# Pcm5102.net
KiCad netlist of a schematic drawn in EAGLE
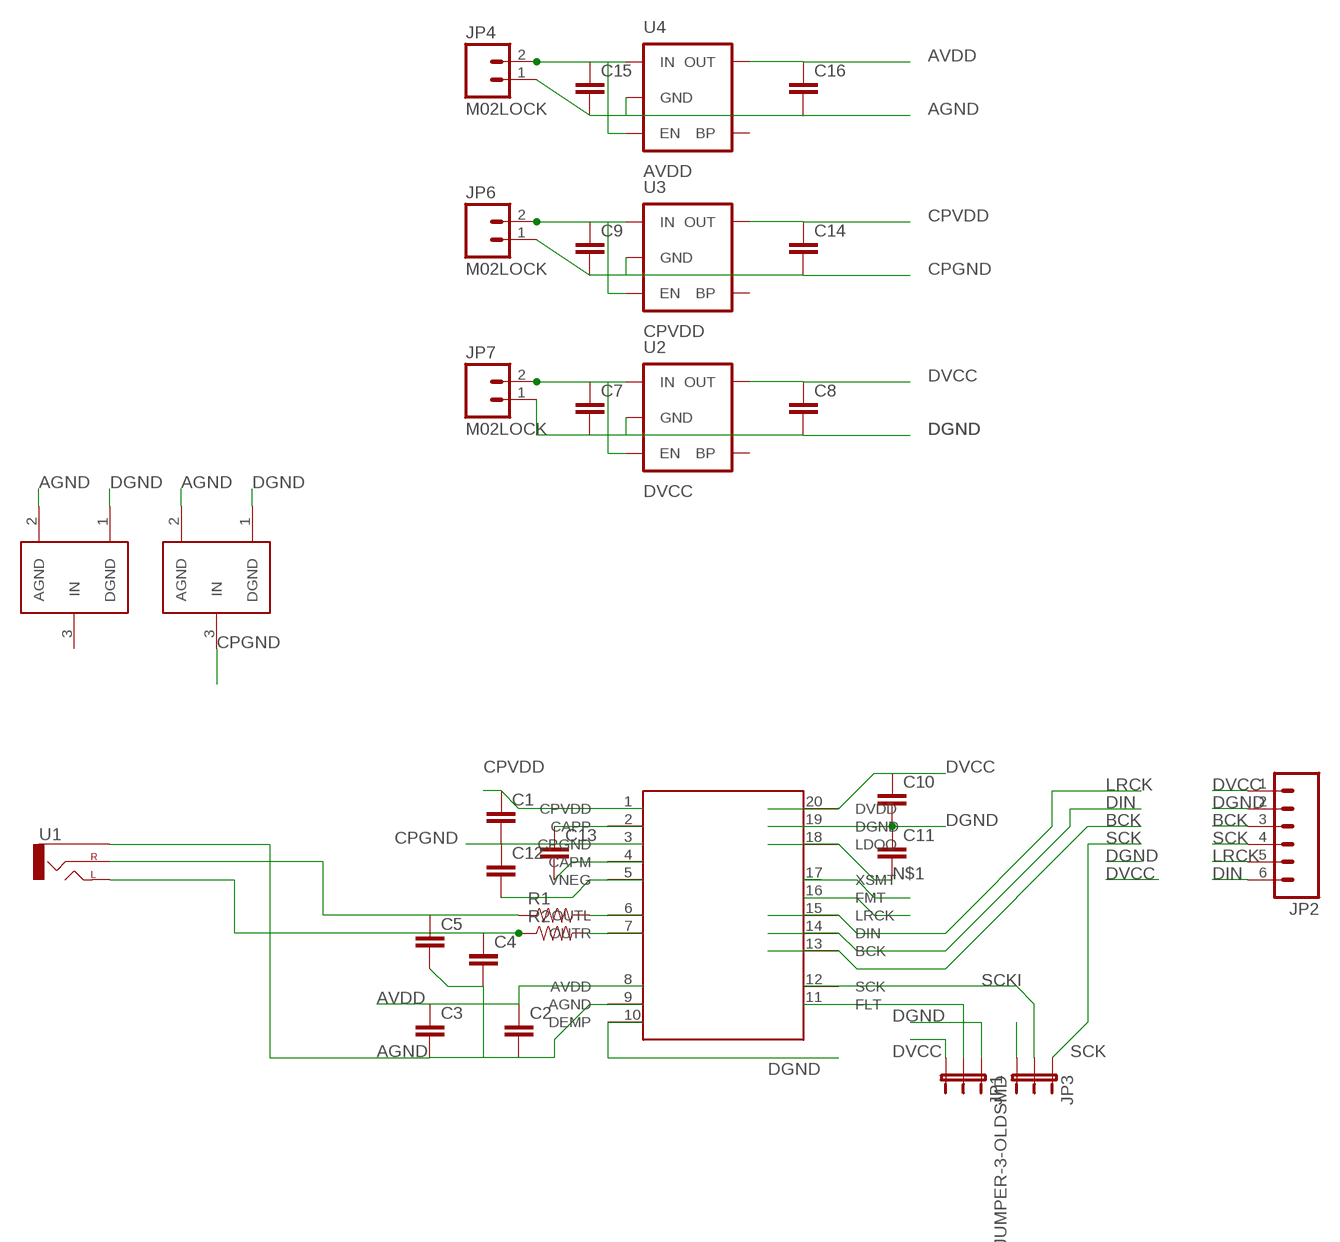
[diagram p0: schematic, sheet 1]

(export (version "E")
  (design (tool "Eeschema 10.0.6"))
  (components
    (comp (ref "C1")
      (value "CAP0805")
      (footprint "eagle-import:0805")
      (libsource (lib "eagle-import") (part "CAP0805"))
    )
    (comp (ref "C2")
      (value "CAP0805")
      (footprint "eagle-import:0805")
      (libsource (lib "eagle-import") (part "CAP0805"))
    )
    (comp (ref "C3")
      (value "CAP0805")
      (footprint "eagle-import:0805")
      (libsource (lib "eagle-import") (part "CAP0805"))
    )
    (comp (ref "C4")
      (value "CAPPTH1")
      (footprint "eagle-import:CAP-PTH-5MM")
      (libsource (lib "eagle-import") (part "CAPPTH1"))
    )
    (comp (ref "C5")
      (value "CAPPTH1")
      (footprint "eagle-import:CAP-PTH-5MM")
      (libsource (lib "eagle-import") (part "CAPPTH1"))
    )
    (comp (ref "C7")
      (value "CAP0805")
      (footprint "eagle-import:0805")
      (libsource (lib "eagle-import") (part "CAP0805"))
    )
    (comp (ref "C8")
      (value "CAP0805")
      (footprint "eagle-import:0805")
      (libsource (lib "eagle-import") (part "CAP0805"))
    )
    (comp (ref "C9")
      (value "CAP0805")
      (footprint "eagle-import:0805")
      (libsource (lib "eagle-import") (part "CAP0805"))
    )
    (comp (ref "C10")
      (value "CAP0805")
      (footprint "eagle-import:0805")
      (libsource (lib "eagle-import") (part "CAP0805"))
    )
    (comp (ref "C11")
      (value "CAP0805")
      (footprint "eagle-import:0805")
      (libsource (lib "eagle-import") (part "CAP0805"))
    )
    (comp (ref "C12")
      (value "CAP0805")
      (footprint "eagle-import:0805")
      (libsource (lib "eagle-import") (part "CAP0805"))
    )
    (comp (ref "C13")
      (value "CAP0805")
      (footprint "eagle-import:0805")
      (libsource (lib "eagle-import") (part "CAP0805"))
    )
    (comp (ref "C14")
      (value "CAP0805")
      (footprint "eagle-import:0805")
      (libsource (lib "eagle-import") (part "CAP0805"))
    )
    (comp (ref "C15")
      (value "CAP0805")
      (footprint "eagle-import:0805")
      (libsource (lib "eagle-import") (part "CAP0805"))
    )
    (comp (ref "C16")
      (value "CAP0805")
      (footprint "eagle-import:0805")
      (libsource (lib "eagle-import") (part "CAP0805"))
    )
    (comp (ref "JP1")
      (value "JUMPER-3-OLDPTH")
      (footprint "eagle-import:1X03")
      (libsource (lib "eagle-import") (part "JUMPER-3-OLDPTH"))
    )
    (comp (ref "JP2")
      (value "M06LOCK")
      (footprint "eagle-import:1X06_LOCK")
      (libsource (lib "eagle-import") (part "M06LOCK"))
    )
    (comp (ref "JP3")
      (value "JUMPER-3-OLDSMD")
      (footprint "eagle-import:SJ_3")
      (libsource (lib "eagle-import") (part "JUMPER-3-OLDSMD"))
    )
    (comp (ref "JP4")
      (value "M02LOCK")
      (footprint "eagle-import:1X02_LOCK")
      (libsource (lib "eagle-import") (part "M02LOCK"))
    )
    (comp (ref "JP6")
      (value "M02LOCK")
      (footprint "eagle-import:1X02_LOCK")
      (libsource (lib "eagle-import") (part "M02LOCK"))
    )
    (comp (ref "JP7")
      (value "M02LOCK")
      (footprint "eagle-import:1X02_LOCK")
      (libsource (lib "eagle-import") (part "M02LOCK"))
    )
    (comp (ref "R1")
      (value "RESISTORPTH-1/4W")
      (footprint "eagle-import:AXIAL-0.4")
      (libsource (lib "eagle-import") (part "RESISTORPTH-1/4W"))
    )
    (comp (ref "R2")
      (value "RESISTORPTH-1/4W")
      (footprint "eagle-import:AXIAL-0.4")
      (libsource (lib "eagle-import") (part "RESISTORPTH-1/4W"))
    )
    (comp (ref "U$1")
      (value "PCM5102")
      (footprint "eagle-import:TSSOP20")
      (libsource (lib "eagle-import") (part "PCM5102"))
    )
    (comp (ref "U$2")
      (value "GND_CONNECT")
      (footprint "eagle-import:GND_CONNECT")
      (libsource (lib "eagle-import") (part "GND_CONNECT"))
    )
    (comp (ref "U$3")
      (value "GND_CONNECT")
      (footprint "eagle-import:GND_CONNECT")
      (libsource (lib "eagle-import") (part "GND_CONNECT"))
    )
    (comp (ref "U1")
      (value "AUDIO-JACKPTH")
      (footprint "eagle-import:AUDIO-JACK")
      (libsource (lib "eagle-import") (part "AUDIO-JACKPTH"))
    )
    (comp (ref "U2")
      (value "DVCC")
      (footprint "eagle-import:SOT23-5")
      (libsource (lib "eagle-import") (part "V_REG_LDOSMD"))
    )
    (comp (ref "U3")
      (value "CPVDD")
      (footprint "eagle-import:SOT23-5")
      (libsource (lib "eagle-import") (part "V_REG_LDOSMD"))
    )
    (comp (ref "U4")
      (value "AVDD")
      (footprint "eagle-import:SOT23-5")
      (libsource (lib "eagle-import") (part "V_REG_LDOSMD"))
    )
  )
  (nets
    (net (code "1") (name "/AGND") (class "Default")
      (node (ref "C15") (pin "2") (pinfunction "2_2") (pintype "passive"))
      (node (ref "C16") (pin "2") (pinfunction "2_2") (pintype "passive"))
      (node (ref "C2") (pin "2") (pinfunction "2_2") (pintype "passive"))
      (node (ref "C3") (pin "2") (pinfunction "2_2") (pintype "passive"))
      (node (ref "C4") (pin "2") (pinfunction "2_2") (pintype "passive"))
      (node (ref "C5") (pin "2") (pinfunction "2_2") (pintype "passive"))
      (node (ref "JP4") (pin "1") (pinfunction "1_1") (pintype "passive"))
      (node (ref "U$1") (pin "9") (pinfunction "AGND_9") (pintype "bidirectional"))
      (node (ref "U$2") (pin "2") (pinfunction "AGND_2") (pintype "bidirectional"))
      (node (ref "U$3") (pin "2") (pinfunction "AGND_2") (pintype "bidirectional"))
      (node (ref "U1") (pin "SLEEVE") (pinfunction "SLEEVE_SLEEVE") (pintype "bidirectional"))
      (node (ref "U4") (pin "2") (pinfunction "GND_2") (pintype "input"))
    )
    (net (code "2") (name "/AVDD") (class "Default")
      (node (ref "C16") (pin "1") (pinfunction "1_1") (pintype "passive"))
      (node (ref "C2") (pin "1") (pinfunction "1_1") (pintype "passive"))
      (node (ref "C3") (pin "1") (pinfunction "1_1") (pintype "passive"))
      (node (ref "U$1") (pin "8") (pinfunction "AVDD_8") (pintype "bidirectional"))
      (node (ref "U4") (pin "5") (pinfunction "OUT_5") (pintype "passive"))
    )
    (net (code "3") (name "/BCK") (class "Default")
      (node (ref "JP2") (pin "3") (pinfunction "3_3") (pintype "passive"))
      (node (ref "U$1") (pin "13") (pinfunction "BCK_13") (pintype "bidirectional"))
    )
    (net (code "4") (name "/CPGND") (class "Default")
      (node (ref "C1") (pin "2") (pinfunction "2_2") (pintype "passive"))
      (node (ref "C12") (pin "1") (pinfunction "1_1") (pintype "passive"))
      (node (ref "C14") (pin "2") (pinfunction "2_2") (pintype "passive"))
      (node (ref "C9") (pin "2") (pinfunction "2_2") (pintype "passive"))
      (node (ref "JP6") (pin "1") (pinfunction "1_1") (pintype "passive"))
      (node (ref "U$1") (pin "3") (pinfunction "CPGND_3") (pintype "bidirectional"))
      (node (ref "U$2") (pin "3") (pinfunction "IN_3") (pintype "bidirectional"))
      (node (ref "U3") (pin "2") (pinfunction "GND_2") (pintype "input"))
    )
    (net (code "5") (name "/CPVDD") (class "Default")
      (node (ref "C1") (pin "1") (pinfunction "1_1") (pintype "passive"))
      (node (ref "C14") (pin "1") (pinfunction "1_1") (pintype "passive"))
      (node (ref "U$1") (pin "1") (pinfunction "CPVDD_1") (pintype "bidirectional"))
      (node (ref "U3") (pin "5") (pinfunction "OUT_5") (pintype "passive"))
    )
    (net (code "6") (name "/DGND") (class "Default")
      (node (ref "C10") (pin "2") (pinfunction "2_2") (pintype "passive"))
      (node (ref "C11") (pin "1") (pinfunction "1_1") (pintype "passive"))
      (node (ref "C7") (pin "2") (pinfunction "2_2") (pintype "passive"))
      (node (ref "C8") (pin "2") (pinfunction "2_2") (pintype "passive"))
      (node (ref "JP1") (pin "1") (pinfunction "1_1") (pintype "passive"))
      (node (ref "JP2") (pin "2") (pinfunction "2_2") (pintype "passive"))
      (node (ref "JP3") (pin "3") (pinfunction "3_3") (pintype "passive"))
      (node (ref "JP7") (pin "1") (pinfunction "1_1") (pintype "passive"))
      (node (ref "U$1") (pin "10") (pinfunction "DEMP_10") (pintype "bidirectional"))
      (node (ref "U$1") (pin "16") (pinfunction "FMT_16") (pintype "bidirectional"))
      (node (ref "U$1") (pin "19") (pinfunction "DGND_19") (pintype "bidirectional"))
      (node (ref "U$2") (pin "1") (pinfunction "DGND_1") (pintype "bidirectional"))
      (node (ref "U$3") (pin "1") (pinfunction "DGND_1") (pintype "bidirectional"))
      (node (ref "U2") (pin "2") (pinfunction "GND_2") (pintype "input"))
    )
    (net (code "7") (name "/DIN") (class "Default")
      (node (ref "JP2") (pin "6") (pinfunction "6_6") (pintype "passive"))
      (node (ref "U$1") (pin "14") (pinfunction "DIN_14") (pintype "bidirectional"))
    )
    (net (code "8") (name "/DVCC") (class "Default")
      (node (ref "C10") (pin "1") (pinfunction "1_1") (pintype "passive"))
      (node (ref "C8") (pin "1") (pinfunction "1_1") (pintype "passive"))
      (node (ref "JP1") (pin "3") (pinfunction "3_3") (pintype "passive"))
      (node (ref "JP2") (pin "1") (pinfunction "1_1") (pintype "passive"))
      (node (ref "U$1") (pin "17") (pinfunction "XSMT_17") (pintype "bidirectional"))
      (node (ref "U$1") (pin "20") (pinfunction "DVDD_20") (pintype "bidirectional"))
      (node (ref "U2") (pin "5") (pinfunction "OUT_5") (pintype "passive"))
    )
    (net (code "9") (name "/LRCK") (class "Default")
      (node (ref "JP2") (pin "5") (pinfunction "5_5") (pintype "passive"))
      (node (ref "U$1") (pin "15") (pinfunction "LRCK_15") (pintype "bidirectional"))
    )
    (net (code "10") (name "/N$1") (class "Default")
      (node (ref "C11") (pin "2") (pinfunction "2_2") (pintype "passive"))
      (node (ref "U$1") (pin "18") (pinfunction "LDOO_18") (pintype "bidirectional"))
    )
    (net (code "11") (name "/SCK") (class "Default")
      (node (ref "JP2") (pin "4") (pinfunction "4_4") (pintype "passive"))
      (node (ref "JP3") (pin "1") (pinfunction "1_1") (pintype "passive"))
    )
    (net (code "12") (name "/SCKI") (class "Default")
      (node (ref "JP3") (pin "2") (pinfunction "2_2") (pintype "passive"))
      (node (ref "U$1") (pin "12") (pinfunction "SCK_12") (pintype "bidirectional"))
    )
    (net (code "13") (name "Net-(R1-1)") (class "Default")
      (node (ref "C5") (pin "1") (pinfunction "1_1") (pintype "passive"))
      (node (ref "R1") (pin "P$1") (pinfunction "1_P$1") (pintype "passive"))
      (node (ref "U1") (pin "RING") (pinfunction "RIGHT_RING") (pintype "bidirectional"))
    )
    (net (code "14") (name "Net-(R1-2)") (class "Default")
      (node (ref "R1") (pin "P$2") (pinfunction "2_P$2") (pintype "passive"))
      (node (ref "U$1") (pin "6") (pinfunction "OUTL_6") (pintype "bidirectional"))
    )
    (net (code "15") (name "Net-(R2-1)") (class "Default")
      (node (ref "C4") (pin "1") (pinfunction "1_1") (pintype "passive"))
      (node (ref "R2") (pin "P$1") (pinfunction "1_P$1") (pintype "passive"))
      (node (ref "U1") (pin "TIP") (pinfunction "LEFT_TIP") (pintype "bidirectional"))
    )
    (net (code "16") (name "Net-(R2-2)") (class "Default")
      (node (ref "R2") (pin "P$2") (pinfunction "2_P$2") (pintype "passive"))
      (node (ref "U$1") (pin "7") (pinfunction "OUTR_7") (pintype "bidirectional"))
    )
    (net (code "17") (name "Net-(U$1-CAPM)") (class "Default")
      (node (ref "C13") (pin "2") (pinfunction "2_2") (pintype "passive"))
      (node (ref "U$1") (pin "4") (pinfunction "CAPM_4") (pintype "bidirectional"))
    )
    (net (code "18") (name "Net-(U$1-CAPP)") (class "Default")
      (node (ref "C13") (pin "1") (pinfunction "1_1") (pintype "passive"))
      (node (ref "U$1") (pin "2") (pinfunction "CAPP_2") (pintype "bidirectional"))
    )
    (net (code "19") (name "Net-(U$1-FLT)") (class "Default")
      (node (ref "JP1") (pin "2") (pinfunction "2_2") (pintype "passive"))
      (node (ref "U$1") (pin "11") (pinfunction "FLT_11") (pintype "bidirectional"))
    )
    (net (code "20") (name "Net-(U$1-VNEG)") (class "Default")
      (node (ref "C12") (pin "2") (pinfunction "2_2") (pintype "passive"))
      (node (ref "U$1") (pin "5") (pinfunction "VNEG_5") (pintype "bidirectional"))
    )
    (net (code "21") (name "Net-(U2-EN)") (class "Default")
      (node (ref "C7") (pin "1") (pinfunction "1_1") (pintype "passive"))
      (node (ref "JP7") (pin "2") (pinfunction "2_2") (pintype "passive"))
      (node (ref "U2") (pin "1") (pinfunction "IN_1") (pintype "input"))
      (node (ref "U2") (pin "3") (pinfunction "EN_3") (pintype "input"))
    )
    (net (code "22") (name "Net-(U3-EN)") (class "Default")
      (node (ref "C9") (pin "1") (pinfunction "1_1") (pintype "passive"))
      (node (ref "JP6") (pin "2") (pinfunction "2_2") (pintype "passive"))
      (node (ref "U3") (pin "1") (pinfunction "IN_1") (pintype "input"))
      (node (ref "U3") (pin "3") (pinfunction "EN_3") (pintype "input"))
    )
    (net (code "23") (name "Net-(U4-EN)") (class "Default")
      (node (ref "C15") (pin "1") (pinfunction "1_1") (pintype "passive"))
      (node (ref "JP4") (pin "2") (pinfunction "2_2") (pintype "passive"))
      (node (ref "U4") (pin "1") (pinfunction "IN_1") (pintype "input"))
      (node (ref "U4") (pin "3") (pinfunction "EN_3") (pintype "input"))
    )
    (net (code "24") (name "unconnected-(U$3-IN-Pad3)") (class "Default")
      (node (ref "U$3") (pin "3") (pinfunction "IN_3") (pintype "bidirectional"))
    )
    (net (code "25") (name "unconnected-(U2-BP-Pad4)") (class "Default")
      (node (ref "U2") (pin "4") (pinfunction "BP_4") (pintype "input"))
    )
    (net (code "26") (name "unconnected-(U3-BP-Pad4)") (class "Default")
      (node (ref "U3") (pin "4") (pinfunction "BP_4") (pintype "input"))
    )
    (net (code "27") (name "unconnected-(U4-BP-Pad4)") (class "Default")
      (node (ref "U4") (pin "4") (pinfunction "BP_4") (pintype "input"))
    )
  )
)
